# CH340G_Basic-5V.net
KiCad netlist of a schematic drawn in EAGLE
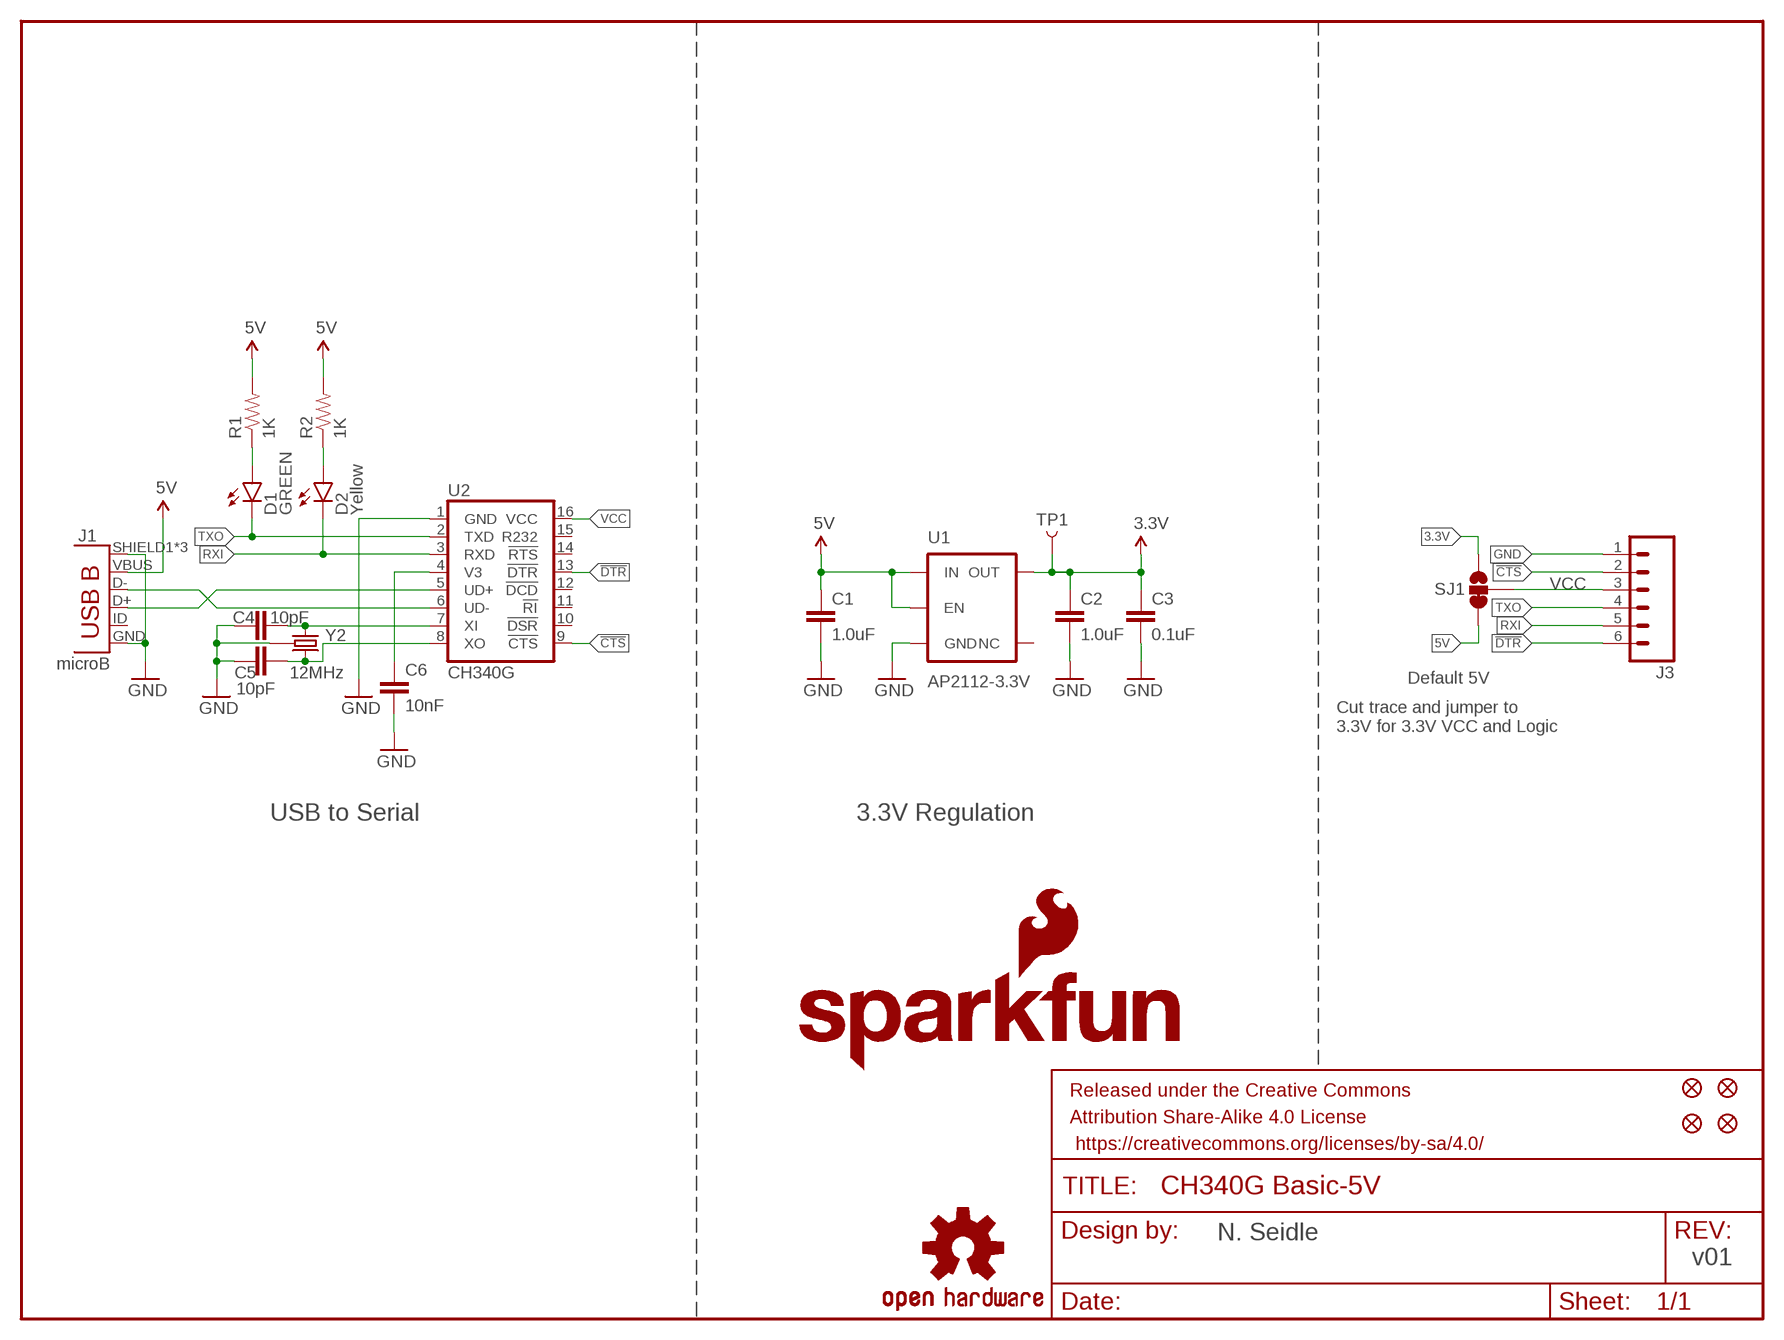
[diagram p0: schematic, sheet 1]

(export (version "E")
  (design (tool "Eeschema 10.0.6"))
  (components
    (comp (ref "C1")
      (value "1.0uF")
      (footprint "eagle-import:0603-CAP")
      (libsource (lib "eagle-import") (part "1.0UF-16V-10%(0603)"))
    )
    (comp (ref "C2")
      (value "1.0uF")
      (footprint "eagle-import:0603-CAP")
      (libsource (lib "eagle-import") (part "1.0UF-16V-10%(0603)"))
    )
    (comp (ref "C3")
      (value "0.1uF")
      (footprint "eagle-import:0603-CAP")
      (libsource (lib "eagle-import") (part "0.1UF-25V(+80/-20%)(0603)"))
    )
    (comp (ref "C4")
      (value "10pF")
      (footprint "eagle-import:0603-CAP")
      (libsource (lib "eagle-import") (part "10PF-50V-5%(0603)"))
    )
    (comp (ref "C5")
      (value "10pF")
      (footprint "eagle-import:0603-CAP")
      (libsource (lib "eagle-import") (part "10PF-50V-5%(0603)"))
    )
    (comp (ref "C6")
      (value "10nF")
      (footprint "eagle-import:0603-CAP")
      (libsource (lib "eagle-import") (part "10NF/10000PF-50V-10%(0603)"))
    )
    (comp (ref "D1")
      (value "GREEN")
      (footprint "eagle-import:LED-0603")
      (libsource (lib "eagle-import") (part "LED-GREEN0603"))
    )
    (comp (ref "D2")
      (value "Yellow")
      (footprint "eagle-import:LED-0603")
      (libsource (lib "eagle-import") (part "LED-YELLOW0603"))
    )
    (comp (ref "FRAME1")
      (value "FRAME-LETTER")
      (footprint "eagle-import:CREATIVE_COMMONS")
      (libsource (lib "eagle-import") (part "FRAME-LETTER"))
    )
    (comp (ref "J1")
      (value "microB")
      (footprint "eagle-import:USB-B-MICRO-SMD_V03")
      (libsource (lib "eagle-import") (part "USB-MICROB{dblquote}"))
    )
    (comp (ref "J3")
      (value "M06SMD-FEMALE-V2")
      (footprint "eagle-import:1X06-SMD-FEMALE-V2")
      (libsource (lib "eagle-import") (part "M06SMD-FEMALE-V2"))
    )
    (comp (ref "JP3")
      (value "FIDUCIAL1X2")
      (footprint "eagle-import:FIDUCIAL-1X2")
      (libsource (lib "eagle-import") (part "FIDUCIAL1X2"))
    )
    (comp (ref "JP4")
      (value "FIDUCIAL1X2")
      (footprint "eagle-import:FIDUCIAL-1X2")
      (libsource (lib "eagle-import") (part "FIDUCIAL1X2"))
    )
    (comp (ref "JP5")
      (value "FIDUCIAL1X2")
      (footprint "eagle-import:FIDUCIAL-1X2")
      (libsource (lib "eagle-import") (part "FIDUCIAL1X2"))
    )
    (comp (ref "JP6")
      (value "FIDUCIAL1X2")
      (footprint "eagle-import:FIDUCIAL-1X2")
      (libsource (lib "eagle-import") (part "FIDUCIAL1X2"))
    )
    (comp (ref "LOGO1")
      (value "OSHW-LOGOS")
      (footprint "eagle-import:OSHW-LOGO-S")
      (libsource (lib "eagle-import") (part "OSHW-LOGOS"))
    )
    (comp (ref "LOGO2")
      (value "SFE_LOGO_FLAME.1_INCH")
      (footprint "eagle-import:SFE_LOGO_FLAME_.1")
      (libsource (lib "eagle-import") (part "SFE_LOGO_FLAME.1_INCH"))
    )
    (comp (ref "LOGO3")
      (value "SFE_LOGO_NAME.1_INCH")
      (footprint "eagle-import:SFE_LOGO_NAME_.1")
      (libsource (lib "eagle-import") (part "SFE_LOGO_NAME.1_INCH"))
    )
    (comp (ref "R1")
      (value "1K")
      (footprint "eagle-import:0603-RES")
      (libsource (lib "eagle-import") (part "1KOHM-1/10W-1%(0603)"))
    )
    (comp (ref "R2")
      (value "1K")
      (footprint "eagle-import:0603-RES")
      (libsource (lib "eagle-import") (part "1KOHM-1/10W-1%(0603)"))
    )
    (comp (ref "SJ1")
      (value "SOLDERJUMPER_2WAYS")
      (footprint "eagle-import:SJ_3")
      (libsource (lib "eagle-import") (part "SOLDERJUMPER_2WAYS"))
    )
    (comp (ref "TP1")
      (value "3.3V TP")
      (footprint "eagle-import:PAD.03X.03")
      (libsource (lib "eagle-import") (part "TEST-POINT3"))
    )
    (comp (ref "U1")
      (value "AP2112-3.3V")
      (footprint "eagle-import:SOT23-5")
      (libsource (lib "eagle-import") (part "V_REG_AP2112K-3.3V"))
    )
    (comp (ref "U2")
      (value "CH340G")
      (footprint "eagle-import:SO016")
      (libsource (lib "eagle-import") (part "CH340GSMD"))
    )
    (comp (ref "Y2")
      (value "12MHz")
      (footprint "eagle-import:CRYSTAL-SMD-3.2X2.5")
      (libsource (lib "eagle-import") (part "CRYSTAL-GROUNDED3.2X2.5"))
    )
  )
  (nets
    (net (code "1") (name "/~{CTS}") (class "Default")
      (node (ref "J3") (pin "2") (pinfunction "2_2") (pintype "passive"))
      (node (ref "U2") (pin "9") (pinfunction "~{CTS}_9") (pintype "bidirectional"))
    )
    (net (code "2") (name "/~{DTR}") (class "Default")
      (node (ref "J3") (pin "6") (pinfunction "6_6") (pintype "passive"))
      (node (ref "U2") (pin "13") (pinfunction "~{DTR}_13") (pintype "bidirectional"))
    )
    (net (code "3") (name "3.3V") (class "Default")
      (node (ref "C2") (pin "1") (pinfunction "1_1") (pintype "passive"))
      (node (ref "C3") (pin "1") (pinfunction "1_1") (pintype "passive"))
      (node (ref "SJ1") (pin "3") (pinfunction "3_3") (pintype "passive"))
      (node (ref "TP1") (pin "P$1") (pinfunction "1_P$1") (pintype "bidirectional"))
      (node (ref "U1") (pin "5") (pinfunction "OUT_5") (pintype "passive"))
    )
    (net (code "4") (name "5V") (class "Default")
      (node (ref "C1") (pin "1") (pinfunction "1_1") (pintype "passive"))
      (node (ref "J1") (pin "VBUS") (pinfunction "VBUS_VBUS") (pintype "bidirectional"))
      (node (ref "R1") (pin "2") (pinfunction "2_2") (pintype "passive"))
      (node (ref "R2") (pin "2") (pinfunction "2_2") (pintype "passive"))
      (node (ref "SJ1") (pin "1") (pinfunction "1_1") (pintype "passive"))
      (node (ref "U1") (pin "1") (pinfunction "IN_1") (pintype "input"))
      (node (ref "U1") (pin "3") (pinfunction "EN_3") (pintype "input"))
    )
    (net (code "5") (name "GND") (class "Default")
      (node (ref "C1") (pin "2") (pinfunction "2_2") (pintype "passive"))
      (node (ref "C2") (pin "2") (pinfunction "2_2") (pintype "passive"))
      (node (ref "C3") (pin "2") (pinfunction "2_2") (pintype "passive"))
      (node (ref "C4") (pin "1") (pinfunction "1_1") (pintype "passive"))
      (node (ref "C5") (pin "1") (pinfunction "1_1") (pintype "passive"))
      (node (ref "C6") (pin "2") (pinfunction "2_2") (pintype "passive"))
      (node (ref "J1") (pin "GND") (pinfunction "GND_GND") (pintype "bidirectional"))
      (node (ref "J1") (pin "SHIELD1") (pinfunction "SHIELD_SHIELD1") (pintype "bidirectional"))
      (node (ref "J1") (pin "SHIELD2") (pinfunction "SHIELD_SHIELD2") (pintype "bidirectional"))
      (node (ref "J1") (pin "SHIELD3") (pinfunction "SHIELD_SHIELD3") (pintype "bidirectional"))
      (node (ref "J3") (pin "1") (pinfunction "1_1") (pintype "passive"))
      (node (ref "U1") (pin "2") (pinfunction "GND_2") (pintype "input"))
      (node (ref "U2") (pin "1") (pinfunction "GND_1") (pintype "bidirectional"))
      (node (ref "Y2") (pin "2") (pinfunction "GND_2") (pintype "passive"))
      (node (ref "Y2") (pin "4") (pinfunction "GND_4") (pintype "passive"))
    )
    (net (code "6") (name "Net-(D1-PadA)") (class "Default")
      (node (ref "D1") (pin "A") (pinfunction "A_A") (pintype "passive"))
      (node (ref "R1") (pin "1") (pinfunction "1_1") (pintype "passive"))
    )
    (net (code "7") (name "Net-(D2-PadA)") (class "Default")
      (node (ref "D2") (pin "A") (pinfunction "A_A") (pintype "passive"))
      (node (ref "R2") (pin "1") (pinfunction "1_1") (pintype "passive"))
    )
    (net (code "8") (name "Net-(U2-UD+)") (class "Default")
      (node (ref "J1") (pin "D+") (pinfunction "D+_D+") (pintype "bidirectional"))
      (node (ref "U2") (pin "5") (pinfunction "UD+_5") (pintype "bidirectional"))
    )
    (net (code "9") (name "Net-(U2-UD-)") (class "Default")
      (node (ref "J1") (pin "D-") (pinfunction "D-_D-") (pintype "bidirectional"))
      (node (ref "U2") (pin "6") (pinfunction "UD-_6") (pintype "bidirectional"))
    )
    (net (code "10") (name "Net-(U2-V3)") (class "Default")
      (node (ref "C6") (pin "1") (pinfunction "1_1") (pintype "passive"))
      (node (ref "U2") (pin "4") (pinfunction "V3_4") (pintype "bidirectional"))
    )
    (net (code "11") (name "Net-(U2-XI)") (class "Default")
      (node (ref "C4") (pin "2") (pinfunction "2_2") (pintype "passive"))
      (node (ref "U2") (pin "7") (pinfunction "XI_7") (pintype "bidirectional"))
      (node (ref "Y2") (pin "1") (pinfunction "1_1") (pintype "passive"))
    )
    (net (code "12") (name "Net-(U2-XO)") (class "Default")
      (node (ref "C5") (pin "2") (pinfunction "2_2") (pintype "passive"))
      (node (ref "U2") (pin "8") (pinfunction "XO_8") (pintype "bidirectional"))
      (node (ref "Y2") (pin "3") (pinfunction "2_3") (pintype "passive"))
    )
    (net (code "13") (name "RXI") (class "Default")
      (node (ref "D2") (pin "C") (pinfunction "C_C") (pintype "passive"))
      (node (ref "J3") (pin "5") (pinfunction "5_5") (pintype "passive"))
      (node (ref "U2") (pin "3") (pinfunction "RXD_3") (pintype "bidirectional"))
    )
    (net (code "14") (name "TXO") (class "Default")
      (node (ref "D1") (pin "C") (pinfunction "C_C") (pintype "passive"))
      (node (ref "J3") (pin "4") (pinfunction "4_4") (pintype "passive"))
      (node (ref "U2") (pin "2") (pinfunction "TXD_2") (pintype "bidirectional"))
    )
    (net (code "15") (name "VCC") (class "Default")
      (node (ref "J3") (pin "3") (pinfunction "3_3") (pintype "passive"))
      (node (ref "SJ1") (pin "2") (pinfunction "2_2") (pintype "passive"))
      (node (ref "U2") (pin "16") (pinfunction "VCC_16") (pintype "bidirectional"))
    )
    (net (code "16") (name "unconnected-(J1-USBID-PadID)") (class "Default")
      (node (ref "J1") (pin "ID") (pinfunction "USBID_ID") (pintype "bidirectional"))
    )
    (net (code "17") (name "unconnected-(U1-NC-Pad4)") (class "Default")
      (node (ref "U1") (pin "4") (pinfunction "NC_4") (pintype "input"))
    )
    (net (code "18") (name "unconnected-(U2-R232-Pad15)") (class "Default")
      (node (ref "U2") (pin "15") (pinfunction "R232_15") (pintype "bidirectional"))
    )
    (net (code "19") (name "unconnected-(U2-~{DCD}-Pad12)") (class "Default")
      (node (ref "U2") (pin "12") (pinfunction "~{DCD}_12") (pintype "bidirectional"))
    )
    (net (code "20") (name "unconnected-(U2-~{DSR}-Pad10)") (class "Default")
      (node (ref "U2") (pin "10") (pinfunction "~{DSR}_10") (pintype "bidirectional"))
    )
    (net (code "21") (name "unconnected-(U2-~{RI}-Pad11)") (class "Default")
      (node (ref "U2") (pin "11") (pinfunction "~{RI}_11") (pintype "bidirectional"))
    )
    (net (code "22") (name "unconnected-(U2-~{RTS}-Pad14)") (class "Default")
      (node (ref "U2") (pin "14") (pinfunction "~{RTS}_14") (pintype "bidirectional"))
    )
  )
)
